# ReflectanceSensor.net
KiCad netlist of a schematic drawn in Altium Designer
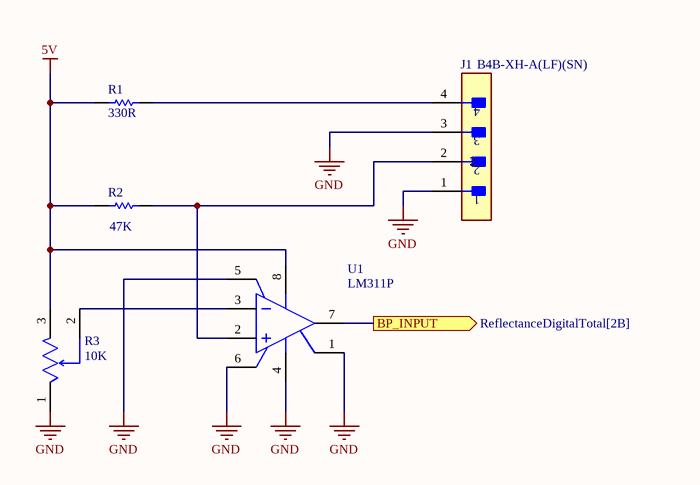
[diagram p0: ReflectanceSensor.SchDoc]

(export (version "E")
  (design (tool "Eeschema 10.0.6"))
  (components
    (comp (ref "J1")
      (value "B4B-XH-A(LF)(SN)")
      (footprint "FP-B4B-XH-A_LF_SN-MFG")
      (description "CONN HEADER VERT 4POS 2.5MM")
      (libsource (lib "Altium Content Vault") (part "299a8cea1bdcbc3624fe62c390fa72c"))
    )
    (comp (ref "R1")
      (value "330R")
      (footprint "RESA60-630X240")
      (description "Axial Resistor, 100 KOhm, +/- 1%, 0.25 W, -55 to 155 degC, 2-Pin THD, RoHS, Bulk")
      (fields (field (name "TOLERANCE") "1%"))
      (libsource (lib "Altium Content Vault") (part "RES-2"))
    )
    (comp (ref "R2")
      (value "47K")
      (footprint "RESA60-630X240")
      (description "Axial Resistor, 100 KOhm, +/- 1%, 0.25 W, -55 to 155 degC, 2-Pin THD, RoHS, Bulk")
      (fields (field (name "TOLERANCE") "1%"))
      (libsource (lib "Altium Content Vault") (part "RES-2"))
    )
    (comp (ref "R3")
      (value "10K")
      (footprint "FP-3296W-MFG")
      (description "TRIMMER 2K OHM 0.5W PC PIN TOP")
      (fields (field (name "TOLERANCE") "10%"))
      (libsource (lib "Altium Content Vault") (part "81a8d1f2e6c155a1fa928b358d1a42a"))
    )
    (comp (ref "U1")
      (value "LM311P")
      (footprint "FP-P0008A-MFG")
      (fields (field (name "TOLERANCE") "1%"))
      (libsource (lib "Altium Content Vault") (part "b2b1c66385073ed7f685b7e01cc60c1"))
    )
  )
  (nets
    (net (code "1") (name "/BP_INPUT") (class "Default")
      (node (ref "U1") (pin "7") (pinfunction "COL_OUT_7") (pintype "open_collector"))
    )
    (net (code "2") (name "5V") (class "Default")
      (node (ref "R1") (pin "1") (pinfunction "1_1") (pintype "passive"))
      (node (ref "R2") (pin "1") (pinfunction "1_1") (pintype "passive"))
      (node (ref "R3") (pin "3") (pinfunction "CW_3") (pintype "passive"))
      (node (ref "U1") (pin "8") (pinfunction "VCC+_8") (pintype "power_in"))
    )
    (net (code "3") (name "GND") (class "Default")
      (node (ref "J1") (pin "1") (pinfunction "1_1") (pintype "passive"))
      (node (ref "J1") (pin "3") (pinfunction "3_3") (pintype "passive"))
      (node (ref "R3") (pin "1") (pinfunction "CCW_1") (pintype "passive"))
      (node (ref "U1") (pin "1") (pinfunction "EMIT_OUT_1") (pintype "open_emitter"))
      (node (ref "U1") (pin "4") (pinfunction "VCC-_4") (pintype "power_in"))
      (node (ref "U1") (pin "5") (pinfunction "BALANCE_5") (pintype "passive"))
      (node (ref "U1") (pin "6") (pinfunction "BAL/STRB_6") (pintype "passive"))
    )
    (net (code "4") (name "Net-(J1-Pad4)") (class "Default")
      (node (ref "J1") (pin "4") (pinfunction "4_4") (pintype "passive"))
      (node (ref "R1") (pin "2") (pinfunction "2_2") (pintype "passive"))
    )
    (net (code "5") (name "Net-(R3-WIPER)") (class "Default")
      (node (ref "R3") (pin "2") (pinfunction "WIPER_2") (pintype "passive"))
      (node (ref "U1") (pin "3") (pinfunction "IN-_3") (pintype "tri_state"))
    )
    (net (code "6") (name "Net-(U1-IN+)") (class "Default")
      (node (ref "J1") (pin "2") (pinfunction "2_2") (pintype "passive"))
      (node (ref "R2") (pin "2") (pinfunction "2_2") (pintype "passive"))
      (node (ref "U1") (pin "2") (pinfunction "IN+_2") (pintype "tri_state"))
    )
  )
)
